# Outlet.net
KiCad netlist of a schematic drawn in EAGLE
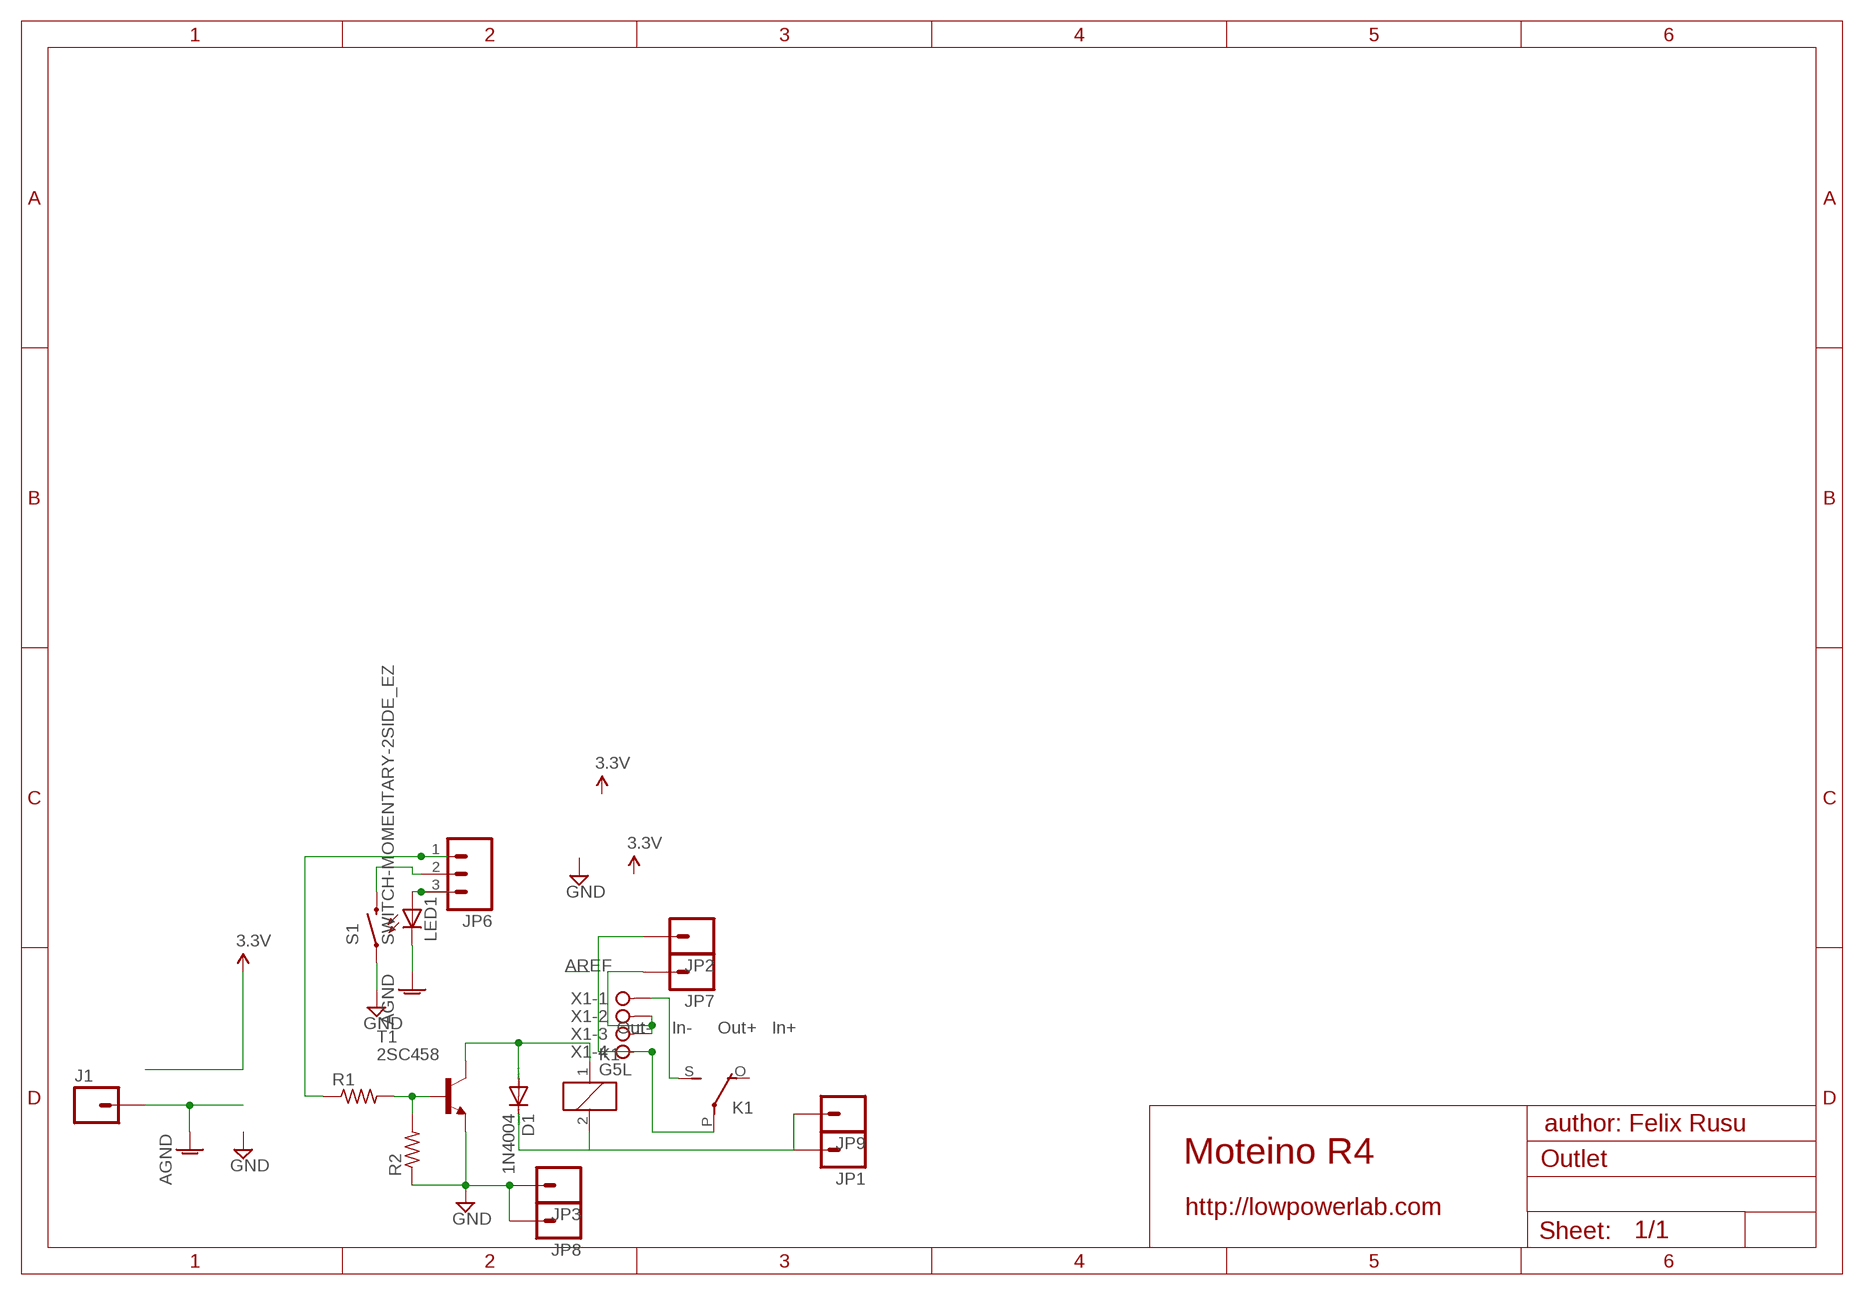
[diagram p0: schematic, sheet 1]

(export (version "E")
  (design (tool "Eeschema 10.0.6"))
  (components
    (comp (ref "D1")
      (value "1N4004")
      (footprint "eagle-import:DO41-10")
      (libsource (lib "eagle-import") (part "1N4004"))
    )
    (comp (ref "J1")
      (value "M01PTH")
      (footprint "eagle-import:1X01")
      (libsource (lib "eagle-import") (part "M01PTH"))
    )
    (comp (ref "JP1")
      (value "M01PTH")
      (footprint "eagle-import:1X01")
      (libsource (lib "eagle-import") (part "M01PTH"))
    )
    (comp (ref "JP2")
      (value "M01PTH")
      (footprint "eagle-import:1X01")
      (libsource (lib "eagle-import") (part "M01PTH"))
    )
    (comp (ref "JP3")
      (value "M01PTH")
      (footprint "eagle-import:1X01")
      (libsource (lib "eagle-import") (part "M01PTH"))
    )
    (comp (ref "JP6")
      (value "M03PTH")
      (footprint "eagle-import:1X03")
      (libsource (lib "eagle-import") (part "M03PTH"))
    )
    (comp (ref "JP7")
      (value "M01PTH")
      (footprint "eagle-import:1X01")
      (libsource (lib "eagle-import") (part "M01PTH"))
    )
    (comp (ref "JP8")
      (value "M01PTH")
      (footprint "eagle-import:1X01")
      (libsource (lib "eagle-import") (part "M01PTH"))
    )
    (comp (ref "JP9")
      (value "M01PTH")
      (footprint "eagle-import:1X01")
      (libsource (lib "eagle-import") (part "M01PTH"))
    )
    (comp (ref "K1")
      (value "G5L")
      (footprint "eagle-import:G5LE")
      (libsource (lib "eagle-import") (part "G5L"))
    )
    (comp (ref "LED1")
      (value "LED3MM")
      (footprint "eagle-import:LED3MM")
      (libsource (lib "eagle-import") (part "LED3MM"))
    )
    (comp (ref "R1")
      (value "R-US_0204/7")
      (footprint "eagle-import:0204_7")
      (libsource (lib "eagle-import") (part "R-US_0204/7"))
    )
    (comp (ref "R2")
      (value "R-US_0204/7")
      (footprint "eagle-import:0204_7")
      (libsource (lib "eagle-import") (part "R-US_0204/7"))
    )
    (comp (ref "S1")
      (value "SWITCH-MOMENTARY-2SIDE_EZ")
      (footprint "eagle-import:TACTILE-PTH-SIDEEZ")
      (libsource (lib "eagle-import") (part "SWITCH-MOMENTARY-2SIDE_EZ"))
    )
    (comp (ref "T1")
      (value "2SC458")
      (footprint "eagle-import:TO92-ECB")
      (libsource (lib "eagle-import") (part "2SC458"))
    )
    (comp (ref "X1")
      (value "Out- In- Out+ In+")
      (footprint "eagle-import:W237-4P")
      (fields (field (name "MF") "In-") (field (name "MPN") "Out-"))
      (libsource (lib "eagle-import") (part "W237-04P"))
    )
  )
  (nets
    (net (code "3") (name "AGND") (class "Default")
      (node (ref "J1") (pin "1") (pinfunction "1_1") (pintype "passive"))
      (node (ref "LED1") (pin "K") (pinfunction "C_K") (pintype "passive"))
    )
    (net (code "4") (name "GND") (class "Default")
      (node (ref "JP3") (pin "1") (pinfunction "1_1") (pintype "passive"))
      (node (ref "JP8") (pin "1") (pinfunction "1_1") (pintype "passive"))
      (node (ref "R2") (pin "1") (pinfunction "1_1") (pintype "passive"))
      (node (ref "S1") (pin "1") (pinfunction "1_1") (pintype "passive"))
      (node (ref "T1") (pin "E") (pinfunction "E_E") (pintype "passive"))
    )
    (net (code "5") (name "Net-(D1-PadA)") (class "Default")
      (node (ref "D1") (pin "A") (pinfunction "A_A") (pintype "passive"))
      (node (ref "K1") (pin "1") (pinfunction "1_1") (pintype "passive"))
      (node (ref "T1") (pin "C") (pinfunction "C_C") (pintype "passive"))
    )
    (net (code "6") (name "Net-(D1-PadC)") (class "Default")
      (node (ref "D1") (pin "C") (pinfunction "C_C") (pintype "passive"))
      (node (ref "JP1") (pin "1") (pinfunction "1_1") (pintype "passive"))
      (node (ref "JP9") (pin "1") (pinfunction "1_1") (pintype "passive"))
      (node (ref "K1") (pin "2") (pinfunction "2_2") (pintype "passive"))
    )
    (net (code "7") (name "Net-(JP6-Pad1)") (class "Default")
      (node (ref "JP6") (pin "1") (pinfunction "1_1") (pintype "passive"))
      (node (ref "R1") (pin "1") (pinfunction "1_1") (pintype "passive"))
    )
    (net (code "8") (name "Net-(JP6-Pad2)") (class "Default")
      (node (ref "JP6") (pin "2") (pinfunction "2_2") (pintype "passive"))
      (node (ref "S1") (pin "2") (pinfunction "2_2") (pintype "passive"))
    )
    (net (code "9") (name "Net-(JP6-Pad3)") (class "Default")
      (node (ref "JP6") (pin "3") (pinfunction "3_3") (pintype "passive"))
      (node (ref "LED1") (pin "A") (pinfunction "A_A") (pintype "passive"))
    )
    (net (code "10") (name "Net-(R1-Pad2)") (class "Default")
      (node (ref "R1") (pin "2") (pinfunction "2_2") (pintype "passive"))
      (node (ref "R2") (pin "2") (pinfunction "2_2") (pintype "passive"))
      (node (ref "T1") (pin "B") (pinfunction "B_B") (pintype "passive"))
    )
    (net (code "11") (name "Net-(X1A-KL)") (class "Default")
      (node (ref "K1") (pin "S") (pinfunction "S_S") (pintype "passive"))
      (node (ref "X1") (pin "1") (pinfunction "KL_1") (pintype "passive"))
    )
    (net (code "12") (name "Net-(X1B-KL)") (class "Default")
      (node (ref "JP7") (pin "1") (pinfunction "1_1") (pintype "passive"))
      (node (ref "X1") (pin "2") (pinfunction "KL_2") (pintype "passive"))
      (node (ref "X1") (pin "3") (pinfunction "KL_3") (pintype "passive"))
    )
    (net (code "13") (name "Net-(X1D-KL)") (class "Default")
      (node (ref "JP2") (pin "1") (pinfunction "1_1") (pintype "passive"))
      (node (ref "K1") (pin "P") (pinfunction "P_P") (pintype "passive"))
      (node (ref "X1") (pin "4") (pinfunction "KL_4") (pintype "passive"))
    )
    (net (code "14") (name "unconnected-(K1-PadO)") (class "Default")
      (node (ref "K1") (pin "O") (pinfunction "O_O") (pintype "passive"))
    )
  )
)
